# LedClock.net
KiCad netlist of a schematic drawn in EAGLE
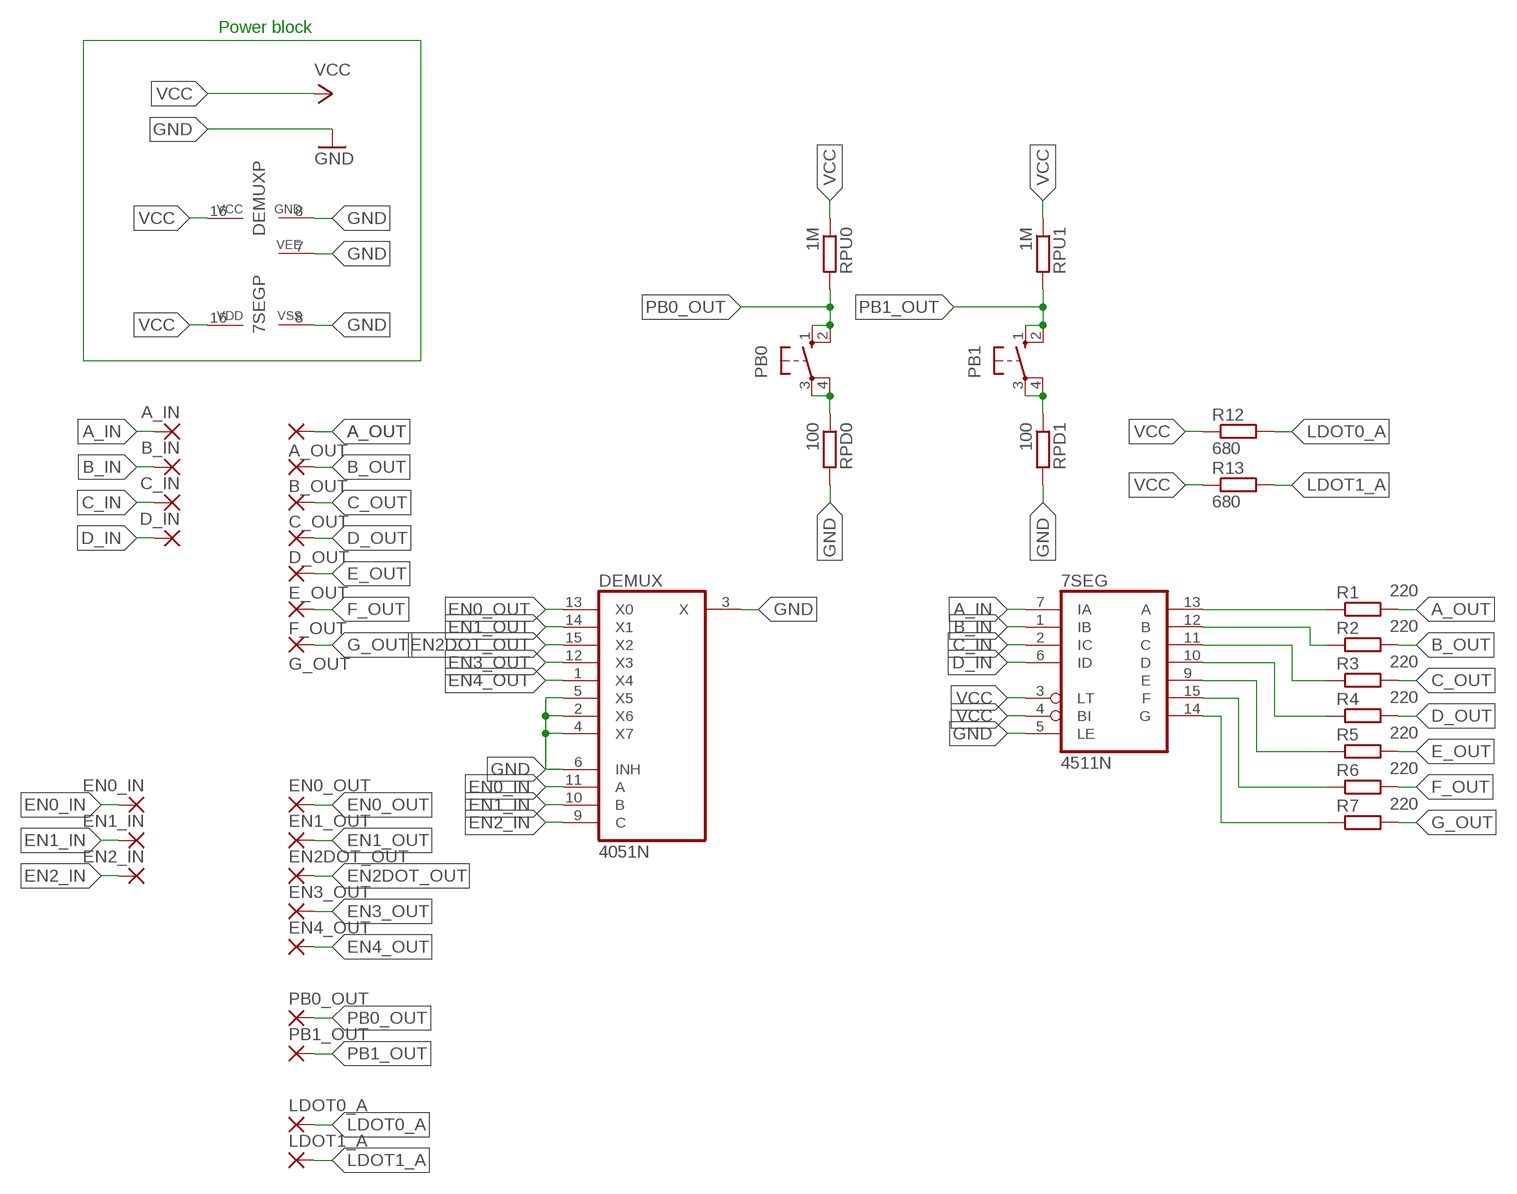
[diagram p0: schematic, sheet 1]

(export (version "E")
  (design (tool "Eeschema 10.0.6"))
  (components
    (comp (ref "7SEG")
      (value "4511N")
      (footprint "eagle-import:DIL16")
      (libsource (lib "eagle-import") (part "4511N"))
    )
    (comp (ref "A_IN")
      (value "2,54/1,0")
      (footprint "eagle-import:2,54_1,0")
      (libsource (lib "eagle-import") (part "2,54/1,0"))
    )
    (comp (ref "A_OUT")
      (value "2,54/1,0")
      (footprint "eagle-import:2,54_1,0")
      (libsource (lib "eagle-import") (part "2,54/1,0"))
    )
    (comp (ref "B_IN")
      (value "2,54/1,0")
      (footprint "eagle-import:2,54_1,0")
      (libsource (lib "eagle-import") (part "2,54/1,0"))
    )
    (comp (ref "B_OUT")
      (value "2,54/1,0")
      (footprint "eagle-import:2,54_1,0")
      (libsource (lib "eagle-import") (part "2,54/1,0"))
    )
    (comp (ref "C_IN")
      (value "2,54/1,0")
      (footprint "eagle-import:2,54_1,0")
      (libsource (lib "eagle-import") (part "2,54/1,0"))
    )
    (comp (ref "C_OUT")
      (value "2,54/1,0")
      (footprint "eagle-import:2,54_1,0")
      (libsource (lib "eagle-import") (part "2,54/1,0"))
    )
    (comp (ref "DEMUX")
      (value "4051N")
      (footprint "eagle-import:DIL16")
      (libsource (lib "eagle-import") (part "4051N"))
    )
    (comp (ref "D_IN")
      (value "2,54/1,0")
      (footprint "eagle-import:2,54_1,0")
      (libsource (lib "eagle-import") (part "2,54/1,0"))
    )
    (comp (ref "D_OUT")
      (value "2,54/1,0")
      (footprint "eagle-import:2,54_1,0")
      (libsource (lib "eagle-import") (part "2,54/1,0"))
    )
    (comp (ref "EN0_IN")
      (value "2,54/1,0")
      (footprint "eagle-import:2,54_1,0")
      (libsource (lib "eagle-import") (part "2,54/1,0"))
    )
    (comp (ref "EN0_OUT")
      (value "2,54/1,0")
      (footprint "eagle-import:2,54_1,0")
      (libsource (lib "eagle-import") (part "2,54/1,0"))
    )
    (comp (ref "EN1_IN")
      (value "2,54/1,0")
      (footprint "eagle-import:2,54_1,0")
      (libsource (lib "eagle-import") (part "2,54/1,0"))
    )
    (comp (ref "EN1_OUT")
      (value "2,54/1,0")
      (footprint "eagle-import:2,54_1,0")
      (libsource (lib "eagle-import") (part "2,54/1,0"))
    )
    (comp (ref "EN2DOT_OUT")
      (value "2,54/1,0")
      (footprint "eagle-import:2,54_1,0")
      (libsource (lib "eagle-import") (part "2,54/1,0"))
    )
    (comp (ref "EN2_IN")
      (value "2,54/1,0")
      (footprint "eagle-import:2,54_1,0")
      (libsource (lib "eagle-import") (part "2,54/1,0"))
    )
    (comp (ref "EN3_OUT")
      (value "2,54/1,0")
      (footprint "eagle-import:2,54_1,0")
      (libsource (lib "eagle-import") (part "2,54/1,0"))
    )
    (comp (ref "EN4_OUT")
      (value "2,54/1,0")
      (footprint "eagle-import:2,54_1,0")
      (libsource (lib "eagle-import") (part "2,54/1,0"))
    )
    (comp (ref "E_OUT")
      (value "2,54/1,0")
      (footprint "eagle-import:2,54_1,0")
      (libsource (lib "eagle-import") (part "2,54/1,0"))
    )
    (comp (ref "F_OUT")
      (value "2,54/1,0")
      (footprint "eagle-import:2,54_1,0")
      (libsource (lib "eagle-import") (part "2,54/1,0"))
    )
    (comp (ref "G_OUT")
      (value "2,54/1,0")
      (footprint "eagle-import:2,54_1,0")
      (libsource (lib "eagle-import") (part "2,54/1,0"))
    )
    (comp (ref "LDOT0_A")
      (value "2,54/1,0")
      (footprint "eagle-import:2,54_1,0")
      (libsource (lib "eagle-import") (part "2,54/1,0"))
    )
    (comp (ref "LDOT1_A")
      (value "2,54/1,0")
      (footprint "eagle-import:2,54_1,0")
      (libsource (lib "eagle-import") (part "2,54/1,0"))
    )
    (comp (ref "PB0")
      (value "10-XX")
      (footprint "eagle-import:B3F-10XX")
      (fields (field (name "MPN") "B3F-1000"))
      (libsource (lib "eagle-import") (part "10-XX"))
    )
    (comp (ref "PB0_OUT")
      (value "2,54/1,0")
      (footprint "eagle-import:2,54_1,0")
      (libsource (lib "eagle-import") (part "2,54/1,0"))
    )
    (comp (ref "PB1")
      (value "10-XX")
      (footprint "eagle-import:B3F-10XX")
      (fields (field (name "MPN") "B3F-1000"))
      (libsource (lib "eagle-import") (part "10-XX"))
    )
    (comp (ref "PB1_OUT")
      (value "2,54/1,0")
      (footprint "eagle-import:2,54_1,0")
      (libsource (lib "eagle-import") (part "2,54/1,0"))
    )
    (comp (ref "R1")
      (value "220")
      (footprint "eagle-import:R1206")
      (libsource (lib "eagle-import") (part "R-EU_R1206"))
    )
    (comp (ref "R2")
      (value "220")
      (footprint "eagle-import:R1206")
      (libsource (lib "eagle-import") (part "R-EU_R1206"))
    )
    (comp (ref "R3")
      (value "220")
      (footprint "eagle-import:R1206")
      (libsource (lib "eagle-import") (part "R-EU_R1206"))
    )
    (comp (ref "R4")
      (value "220")
      (footprint "eagle-import:R1206")
      (libsource (lib "eagle-import") (part "R-EU_R1206"))
    )
    (comp (ref "R5")
      (value "220")
      (footprint "eagle-import:R1206")
      (libsource (lib "eagle-import") (part "R-EU_R1206"))
    )
    (comp (ref "R6")
      (value "220")
      (footprint "eagle-import:R1206")
      (libsource (lib "eagle-import") (part "R-EU_R1206"))
    )
    (comp (ref "R7")
      (value "220")
      (footprint "eagle-import:R1206")
      (libsource (lib "eagle-import") (part "R-EU_R1206"))
    )
    (comp (ref "R12")
      (value "680")
      (footprint "eagle-import:R1206")
      (libsource (lib "eagle-import") (part "R-EU_R1206"))
    )
    (comp (ref "R13")
      (value "680")
      (footprint "eagle-import:R1206")
      (libsource (lib "eagle-import") (part "R-EU_R1206"))
    )
    (comp (ref "RPD0")
      (value "100")
      (footprint "eagle-import:R1206")
      (libsource (lib "eagle-import") (part "R-EU_R1206"))
    )
    (comp (ref "RPD1")
      (value "100")
      (footprint "eagle-import:R1206")
      (libsource (lib "eagle-import") (part "R-EU_R1206"))
    )
    (comp (ref "RPU0")
      (value "1M")
      (footprint "eagle-import:R1206")
      (libsource (lib "eagle-import") (part "R-EU_R1206"))
    )
    (comp (ref "RPU1")
      (value "1M")
      (footprint "eagle-import:R1206")
      (libsource (lib "eagle-import") (part "R-EU_R1206"))
    )
  )
  (nets
    (net (code "1") (name "A_IN") (class "Default")
      (node (ref "7SEG") (pin "7") (pinfunction "IA_7") (pintype "input"))
      (node (ref "A_IN") (pin "1") (pinfunction "P_1") (pintype "passive"))
    )
    (net (code "2") (name "A_OUT") (class "Default")
      (node (ref "A_OUT") (pin "1") (pinfunction "P_1") (pintype "passive"))
      (node (ref "R1") (pin "2") (pinfunction "2_2") (pintype "passive"))
    )
    (net (code "3") (name "B_IN") (class "Default")
      (node (ref "7SEG") (pin "1") (pinfunction "IB_1") (pintype "input"))
      (node (ref "B_IN") (pin "1") (pinfunction "P_1") (pintype "passive"))
    )
    (net (code "4") (name "B_OUT") (class "Default")
      (node (ref "B_OUT") (pin "1") (pinfunction "P_1") (pintype "passive"))
      (node (ref "R2") (pin "2") (pinfunction "2_2") (pintype "passive"))
    )
    (net (code "5") (name "C_IN") (class "Default")
      (node (ref "7SEG") (pin "2") (pinfunction "IC_2") (pintype "input"))
      (node (ref "C_IN") (pin "1") (pinfunction "P_1") (pintype "passive"))
    )
    (net (code "6") (name "C_OUT") (class "Default")
      (node (ref "C_OUT") (pin "1") (pinfunction "P_1") (pintype "passive"))
      (node (ref "R3") (pin "2") (pinfunction "2_2") (pintype "passive"))
    )
    (net (code "7") (name "D_IN") (class "Default")
      (node (ref "7SEG") (pin "6") (pinfunction "ID_6") (pintype "input"))
      (node (ref "D_IN") (pin "1") (pinfunction "P_1") (pintype "passive"))
    )
    (net (code "8") (name "D_OUT") (class "Default")
      (node (ref "D_OUT") (pin "1") (pinfunction "P_1") (pintype "passive"))
      (node (ref "R4") (pin "2") (pinfunction "2_2") (pintype "passive"))
    )
    (net (code "9") (name "EN0_IN") (class "Default")
      (node (ref "DEMUX") (pin "11") (pinfunction "A_11") (pintype "input"))
      (node (ref "EN0_IN") (pin "1") (pinfunction "P_1") (pintype "passive"))
    )
    (net (code "10") (name "EN0_OUT") (class "Default")
      (node (ref "DEMUX") (pin "13") (pinfunction "X0_13") (pintype "bidirectional"))
      (node (ref "EN0_OUT") (pin "1") (pinfunction "P_1") (pintype "passive"))
    )
    (net (code "11") (name "EN1_IN") (class "Default")
      (node (ref "DEMUX") (pin "10") (pinfunction "B_10") (pintype "input"))
      (node (ref "EN1_IN") (pin "1") (pinfunction "P_1") (pintype "passive"))
    )
    (net (code "12") (name "EN1_OUT") (class "Default")
      (node (ref "DEMUX") (pin "14") (pinfunction "X1_14") (pintype "bidirectional"))
      (node (ref "EN1_OUT") (pin "1") (pinfunction "P_1") (pintype "passive"))
    )
    (net (code "13") (name "EN2DOT_OUT") (class "Default")
      (node (ref "DEMUX") (pin "15") (pinfunction "X2_15") (pintype "bidirectional"))
      (node (ref "EN2DOT_OUT") (pin "1") (pinfunction "P_1") (pintype "passive"))
    )
    (net (code "14") (name "EN2_IN") (class "Default")
      (node (ref "DEMUX") (pin "9") (pinfunction "C_9") (pintype "input"))
      (node (ref "EN2_IN") (pin "1") (pinfunction "P_1") (pintype "passive"))
    )
    (net (code "15") (name "EN3_OUT") (class "Default")
      (node (ref "DEMUX") (pin "12") (pinfunction "X3_12") (pintype "bidirectional"))
      (node (ref "EN3_OUT") (pin "1") (pinfunction "P_1") (pintype "passive"))
    )
    (net (code "16") (name "EN4_OUT") (class "Default")
      (node (ref "DEMUX") (pin "1") (pinfunction "X4_1") (pintype "bidirectional"))
      (node (ref "EN4_OUT") (pin "1") (pinfunction "P_1") (pintype "passive"))
    )
    (net (code "17") (name "E_OUT") (class "Default")
      (node (ref "E_OUT") (pin "1") (pinfunction "P_1") (pintype "passive"))
      (node (ref "R5") (pin "2") (pinfunction "2_2") (pintype "passive"))
    )
    (net (code "18") (name "F_OUT") (class "Default")
      (node (ref "F_OUT") (pin "1") (pinfunction "P_1") (pintype "passive"))
      (node (ref "R6") (pin "2") (pinfunction "2_2") (pintype "passive"))
    )
    (net (code "19") (name "GND") (class "Default")
      (node (ref "7SEG") (pin "5") (pinfunction "LE_5") (pintype "input"))
      (node (ref "7SEG") (pin "8") (pinfunction "VSS_8") (pintype "power_in"))
      (node (ref "DEMUX") (pin "2") (pinfunction "X6_2") (pintype "bidirectional"))
      (node (ref "DEMUX") (pin "3") (pinfunction "X_3") (pintype "bidirectional"))
      (node (ref "DEMUX") (pin "4") (pinfunction "X7_4") (pintype "bidirectional"))
      (node (ref "DEMUX") (pin "5") (pinfunction "X5_5") (pintype "bidirectional"))
      (node (ref "DEMUX") (pin "6") (pinfunction "INH_6") (pintype "input"))
      (node (ref "DEMUX") (pin "7") (pinfunction "VEE_7") (pintype "power_in"))
      (node (ref "DEMUX") (pin "8") (pinfunction "GND_8") (pintype "power_in"))
      (node (ref "RPD0") (pin "2") (pinfunction "2_2") (pintype "passive"))
      (node (ref "RPD1") (pin "2") (pinfunction "2_2") (pintype "passive"))
    )
    (net (code "20") (name "G_OUT") (class "Default")
      (node (ref "G_OUT") (pin "1") (pinfunction "P_1") (pintype "passive"))
      (node (ref "R7") (pin "2") (pinfunction "2_2") (pintype "passive"))
    )
    (net (code "21") (name "LDOT0_A") (class "Default")
      (node (ref "LDOT0_A") (pin "1") (pinfunction "P_1") (pintype "passive"))
      (node (ref "R12") (pin "2") (pinfunction "2_2") (pintype "passive"))
    )
    (net (code "22") (name "LDOT1_A") (class "Default")
      (node (ref "LDOT1_A") (pin "1") (pinfunction "P_1") (pintype "passive"))
      (node (ref "R13") (pin "2") (pinfunction "2_2") (pintype "passive"))
    )
    (net (code "23") (name "Net-(7SEGA-A)") (class "Default")
      (node (ref "7SEG") (pin "13") (pinfunction "A_13") (pintype "output"))
      (node (ref "R1") (pin "1") (pinfunction "1_1") (pintype "passive"))
    )
    (net (code "24") (name "Net-(7SEGA-B)") (class "Default")
      (node (ref "7SEG") (pin "12") (pinfunction "B_12") (pintype "output"))
      (node (ref "R2") (pin "1") (pinfunction "1_1") (pintype "passive"))
    )
    (net (code "25") (name "Net-(7SEGA-C)") (class "Default")
      (node (ref "7SEG") (pin "11") (pinfunction "C_11") (pintype "output"))
      (node (ref "R3") (pin "1") (pinfunction "1_1") (pintype "passive"))
    )
    (net (code "26") (name "Net-(7SEGA-D)") (class "Default")
      (node (ref "7SEG") (pin "10") (pinfunction "D_10") (pintype "output"))
      (node (ref "R4") (pin "1") (pinfunction "1_1") (pintype "passive"))
    )
    (net (code "27") (name "Net-(7SEGA-E)") (class "Default")
      (node (ref "7SEG") (pin "9") (pinfunction "E_9") (pintype "output"))
      (node (ref "R5") (pin "1") (pinfunction "1_1") (pintype "passive"))
    )
    (net (code "28") (name "Net-(7SEGA-F)") (class "Default")
      (node (ref "7SEG") (pin "15") (pinfunction "F_15") (pintype "output"))
      (node (ref "R6") (pin "1") (pinfunction "1_1") (pintype "passive"))
    )
    (net (code "29") (name "Net-(7SEGA-G)") (class "Default")
      (node (ref "7SEG") (pin "14") (pinfunction "G_14") (pintype "output"))
      (node (ref "R7") (pin "1") (pinfunction "1_1") (pintype "passive"))
    )
    (net (code "30") (name "Net-(PB0-P)") (class "Default")
      (node (ref "PB0") (pin "3") (pinfunction "P_3") (pintype "passive"))
      (node (ref "PB0") (pin "4") (pinfunction "P1_4") (pintype "passive"))
      (node (ref "RPD0") (pin "1") (pinfunction "1_1") (pintype "passive"))
    )
    (net (code "31") (name "Net-(PB1-P)") (class "Default")
      (node (ref "PB1") (pin "3") (pinfunction "P_3") (pintype "passive"))
      (node (ref "PB1") (pin "4") (pinfunction "P1_4") (pintype "passive"))
      (node (ref "RPD1") (pin "1") (pinfunction "1_1") (pintype "passive"))
    )
    (net (code "32") (name "PB0_OUT") (class "Default")
      (node (ref "PB0") (pin "1") (pinfunction "S_1") (pintype "passive"))
      (node (ref "PB0") (pin "2") (pinfunction "S1_2") (pintype "passive"))
      (node (ref "PB0_OUT") (pin "1") (pinfunction "P_1") (pintype "passive"))
      (node (ref "RPU0") (pin "2") (pinfunction "2_2") (pintype "passive"))
    )
    (net (code "33") (name "PB1_OUT") (class "Default")
      (node (ref "PB1") (pin "1") (pinfunction "S_1") (pintype "passive"))
      (node (ref "PB1") (pin "2") (pinfunction "S1_2") (pintype "passive"))
      (node (ref "PB1_OUT") (pin "1") (pinfunction "P_1") (pintype "passive"))
      (node (ref "RPU1") (pin "2") (pinfunction "2_2") (pintype "passive"))
    )
    (net (code "34") (name "VCC") (class "Default")
      (node (ref "7SEG") (pin "16") (pinfunction "VDD_16") (pintype "power_in"))
      (node (ref "7SEG") (pin "3") (pinfunction "LT_3") (pintype "input"))
      (node (ref "7SEG") (pin "4") (pinfunction "BI_4") (pintype "input"))
      (node (ref "DEMUX") (pin "16") (pinfunction "VCC_16") (pintype "power_in"))
      (node (ref "R12") (pin "1") (pinfunction "1_1") (pintype "passive"))
      (node (ref "R13") (pin "1") (pinfunction "1_1") (pintype "passive"))
      (node (ref "RPU0") (pin "1") (pinfunction "1_1") (pintype "passive"))
      (node (ref "RPU1") (pin "1") (pinfunction "1_1") (pintype "passive"))
    )
  )
)
